# ADC_Core.net
KiCad netlist of a schematic drawn in Altium Designer
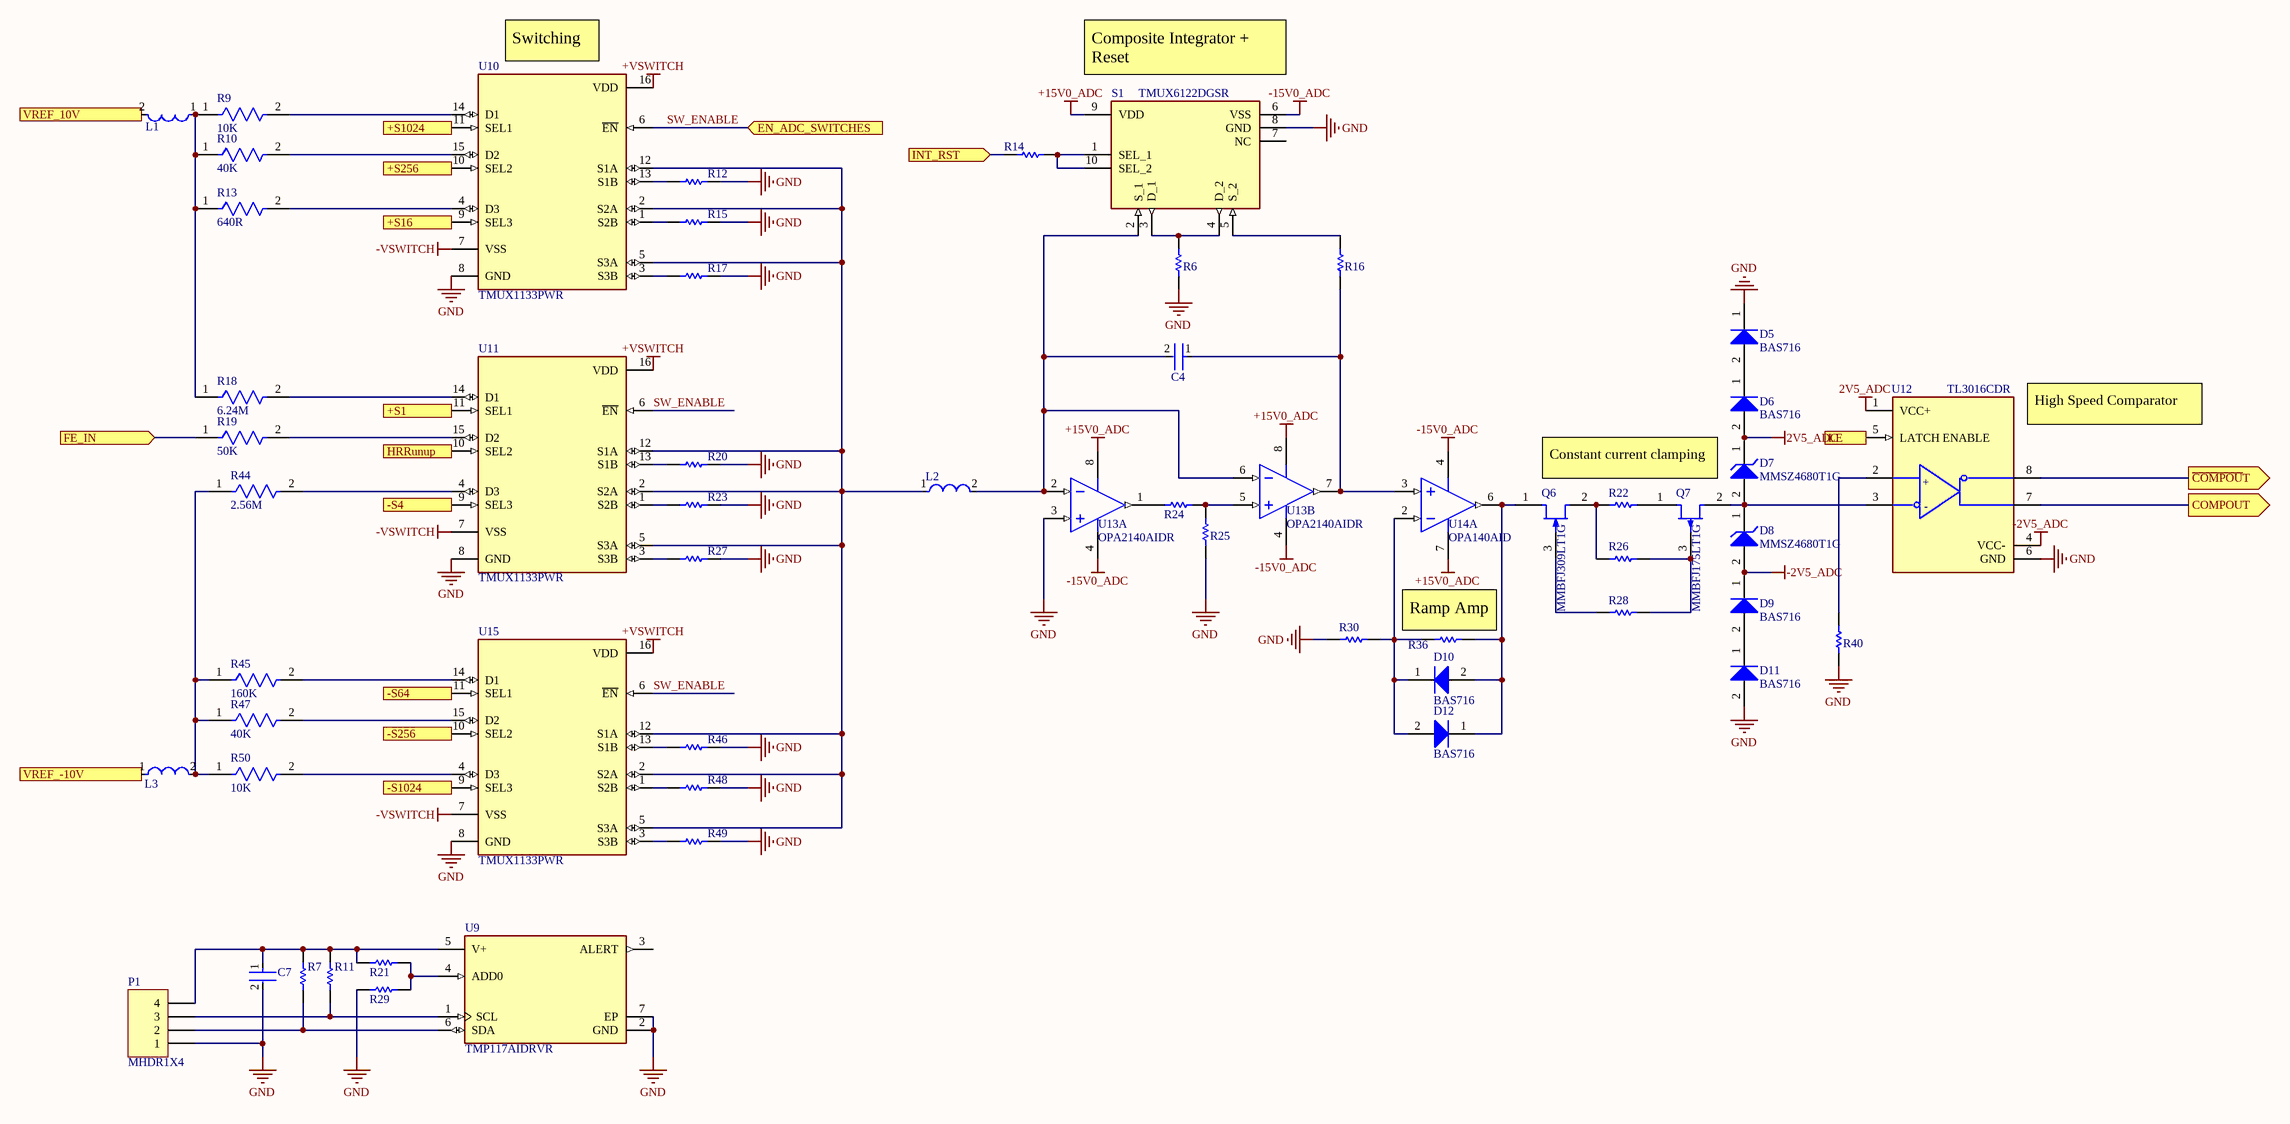
[diagram p0: ADC_Core.SchDoc]

(export (version "E")
  (design (tool "Eeschema 10.0.6"))
  (components
    (comp (ref "C4")
      (value "C1206C331J5GACTU")
      (footprint "FP-C1206C-EB-MFG")
      (description "CAP CER 330PF 50V 5% NP0 1206")
      (fields
        (field (name "MANUFACTURER") "KEMET")
        (field (name "OCTOPART") "https://octopart.com/c1206c331j5gactu-kemet-3859988")
      )
      (libsource (lib "Altium Content Vault") (part "b4654b650e69147ec39a6b967a45e02"))
    )
    (comp (ref "C7")
      (value "C0402C104K8PACTU")
      (footprint "FP-C0402-BB-MFG")
      (description "C0402 0.10 μF X5R 10.00% 10 V")
      (fields (field (name "MANUFACTURER") "Kemet"))
      (libsource (lib "Altium Content Vault") (part "b4654b650e69147ec39a6b967a45e02"))
    )
    (comp (ref "D5")
      (value "BAS716")
      (footprint "ONSC-SOD-523-2-502-01_V")
      (description "Schottky Barrier Diode, 2-Pin SOD-523, Pb-Free, Tape and Reel")
      (fields (field (name "PARTNUMBER") "BAT54XV2T5G") (field (name "MANUFACTURER") "On Semiconductor"))
      (libsource (lib "Altium Content Vault") (part "ONSC-D-K1A2-2"))
    )
    (comp (ref "D6")
      (value "BAS716")
      (footprint "ONSC-SOD-523-2-502-01_V")
      (description "Schottky Barrier Diode, 2-Pin SOD-523, Pb-Free, Tape and Reel")
      (fields (field (name "PARTNUMBER") "BAT54XV2T5G") (field (name "MANUFACTURER") "On Semiconductor"))
      (libsource (lib "Altium Content Vault") (part "ONSC-D-K1A2-2"))
    )
    (comp (ref "D7")
      (value "MMSZ4680T1G")
      (footprint "ONSC-SOD-123-2-425-04_V")
      (description "Zener Voltage Regulator, 500 mW, 2-Pin SOD-123, Pb-Free, Tape and Reel")
      (fields (field (name "MANUFACTURER") "On Semiconductor"))
      (libsource (lib "Altium Content Vault") (part "ONSC-K1A2-2"))
    )
    (comp (ref "D8")
      (value "MMSZ4680T1G")
      (footprint "ONSC-SOD-123-2-425-04_V")
      (description "Zener Voltage Regulator, 500 mW, 2-Pin SOD-123, Pb-Free, Tape and Reel")
      (fields (field (name "MANUFACTURER") "On Semiconductor"))
      (libsource (lib "Altium Content Vault") (part "ONSC-K1A2-2"))
    )
    (comp (ref "D9")
      (value "BAS716")
      (footprint "ONSC-SOD-523-2-502-01_V")
      (description "Schottky Barrier Diode, 2-Pin SOD-523, Pb-Free, Tape and Reel")
      (fields (field (name "PARTNUMBER") "BAT54XV2T5G") (field (name "MANUFACTURER") "On Semiconductor"))
      (libsource (lib "Altium Content Vault") (part "ONSC-D-K1A2-2"))
    )
    (comp (ref "D10")
      (value "BAS716")
      (footprint "ONSC-SOD-523-2-502-01_V")
      (description "Schottky Barrier Diode, 2-Pin SOD-523, Pb-Free, Tape and Reel")
      (fields (field (name "PARTNUMBER") "BAT54XV2T5G") (field (name "MANUFACTURER") "On Semiconductor"))
      (libsource (lib "Altium Content Vault") (part "ONSC-D-K1A2-2"))
    )
    (comp (ref "D11")
      (value "BAS716")
      (footprint "ONSC-SOD-523-2-502-01_V")
      (description "Schottky Barrier Diode, 2-Pin SOD-523, Pb-Free, Tape and Reel")
      (fields (field (name "PARTNUMBER") "BAT54XV2T5G") (field (name "MANUFACTURER") "On Semiconductor"))
      (libsource (lib "Altium Content Vault") (part "ONSC-D-K1A2-2"))
    )
    (comp (ref "D12")
      (value "BAS716")
      (footprint "ONSC-SOD-523-2-502-01_V")
      (description "Schottky Barrier Diode, 2-Pin SOD-523, Pb-Free, Tape and Reel")
      (fields (field (name "PARTNUMBER") "BAT54XV2T5G") (field (name "MANUFACTURER") "On Semiconductor"))
      (libsource (lib "Altium Content Vault") (part "ONSC-D-K1A2-2"))
    )
    (comp (ref "L1")
      (value "LQW15ANR10J00D")
      (footprint "FP-LQW15AN_00-W0_5-0_1-MFG")
      (description "Wire Wound RF Inductor 100nH ±5% 120mA 2.52Ω 0402 (1005)")
      (fields (field (name "TOLERANCE") "5%"))
      (libsource (lib "Altium Content Vault") (part "725321dda6339637d4d059423bc1c3c"))
    )
    (comp (ref "L2")
      (value "LQW15ANR10J00D")
      (footprint "FP-LQW15AN_00-W0_5-0_1-MFG")
      (description "Wire Wound RF Inductor 100nH ±5% 120mA 2.52Ω 0402 (1005)")
      (fields (field (name "TOLERANCE") "5%"))
      (libsource (lib "Altium Content Vault") (part "725321dda6339637d4d059423bc1c3c"))
    )
    (comp (ref "L3")
      (value "LQW15ANR10J00D")
      (footprint "FP-LQW15AN_00-W0_5-0_1-MFG")
      (description "Wire Wound RF Inductor 100nH ±5% 120mA 2.52Ω 0402 (1005)")
      (fields (field (name "TOLERANCE") "5%"))
      (libsource (lib "Altium Content Vault") (part "725321dda6339637d4d059423bc1c3c"))
    )
    (comp (ref "P1")
      (value "MHDR1X4")
      (footprint "MHDR1X4")
      (description "Header, 4-Pin")
      (fields (field (name "PUBLISHER") "Altium Limited"))
      (libsource (lib "Miscellaneous Connectors") (part "MHDR1X4"))
    )
    (comp (ref "Q6")
      (value "MMBFJ309LT1G")
      (footprint "ONSC-SOT-23-3-318-08_V")
      (description "JFET - VHF / UHF Amplifier Transistor, N-Channel, 3-Pin SOT-23, Pb-Free, Tape and Reel")
      (fields (field (name "MANUFACTURER") "On Semiconductor"))
      (libsource (lib "Altium Content Vault") (part "ONSC-JFET-D1S2G3-3-B"))
    )
    (comp (ref "Q7")
      (value "MMBFJ175LT1G")
      (footprint "ONSC-SOT-23-3-318-08_V")
      (description "JFET Chopper, P-Channel - Depletion, 3-Pin SOT-23, Pb-Free, Tape and Reel")
      (fields (field (name "MANUFACTURER") "On Semiconductor"))
      (libsource (lib "Altium Content Vault") (part "ONSC-JFET-D1S2G3-3-C"))
    )
    (comp (ref "R6")
      (value "ERJ-3GEYJ202V")
      (footprint "RESC1608X55X30ML15T15")
      (fields (field (name "MANUFACTURER") "Panasonic"))
      (libsource (lib "Altium Content Vault") (part "RES"))
    )
    (comp (ref "R7")
      (value "CRCW04021K20FKED")
      (footprint "RESC1005X40X25NL05T05")
      (fields (field (name "MANUFACTURER") "Vishay Dale"))
      (libsource (lib "Altium Content Vault") (part "RES"))
    )
    (comp (ref "R9")
      (value "10K")
      (footprint "FP-RC1206-MFG")
      (description "RES SMD 0 OHM JUMPER 1/4W 1206")
      (fields
        (field (name "MANUFACTURER PART NUMBER") "RC1206JR-070RL")
        (field (name "MANUFACTURER") "YAGEO")
      )
      (libsource (lib "Altium Content Vault") (part "1029c3af85768c4190bb7ad29bc67b5"))
    )
    (comp (ref "R10")
      (value "40K")
      (footprint "FP-RC1206-MFG")
      (description "RES SMD 0 OHM JUMPER 1/4W 1206")
      (fields
        (field (name "MANUFACTURER PART NUMBER") "RC1206JR-070RL")
        (field (name "MANUFACTURER") "YAGEO")
      )
      (libsource (lib "Altium Content Vault") (part "1029c3af85768c4190bb7ad29bc67b5"))
    )
    (comp (ref "R11")
      (value "CRCW04021K20FKED")
      (footprint "RESC1005X40X25NL05T05")
      (fields (field (name "MANUFACTURER") "Vishay Dale"))
      (libsource (lib "Altium Content Vault") (part "RES"))
    )
    (comp (ref "R12")
      (value "ERJ-3GEYJ202V")
      (footprint "RESC1608X55X30ML15T15")
      (fields (field (name "MANUFACTURER") "Panasonic"))
      (libsource (lib "Altium Content Vault") (part "RES"))
    )
    (comp (ref "R13")
      (value "640R")
      (footprint "FP-RC1206-MFG")
      (description "RES SMD 0 OHM JUMPER 1/4W 1206")
      (fields
        (field (name "MANUFACTURER PART NUMBER") "RC1206JR-070RL")
        (field (name "MANUFACTURER") "YAGEO")
      )
      (libsource (lib "Altium Content Vault") (part "1029c3af85768c4190bb7ad29bc67b5"))
    )
    (comp (ref "R14")
      (value "ERJ-3GEYJ202V")
      (footprint "RESC1608X55X30ML15T15")
      (fields (field (name "MANUFACTURER") "Panasonic"))
      (libsource (lib "Altium Content Vault") (part "RES"))
    )
    (comp (ref "R15")
      (value "ERJ-3GEYJ202V")
      (footprint "RESC1608X55X30ML15T15")
      (fields (field (name "MANUFACTURER") "Panasonic"))
      (libsource (lib "Altium Content Vault") (part "RES"))
    )
    (comp (ref "R16")
      (value "ERJ-3GEYJ202V")
      (footprint "RESC1608X55X30ML15T15")
      (fields (field (name "MANUFACTURER") "Panasonic"))
      (libsource (lib "Altium Content Vault") (part "RES"))
    )
    (comp (ref "R17")
      (value "ERJ-3GEYJ202V")
      (footprint "RESC1608X55X30ML15T15")
      (fields (field (name "MANUFACTURER") "Panasonic"))
      (libsource (lib "Altium Content Vault") (part "RES"))
    )
    (comp (ref "R18")
      (value "6.24M")
      (footprint "FP-RC1206-MFG")
      (description "RES SMD 0 OHM JUMPER 1/4W 1206")
      (fields
        (field (name "MANUFACTURER PART NUMBER") "RC1206JR-070RL")
        (field (name "MANUFACTURER") "YAGEO")
      )
      (libsource (lib "Altium Content Vault") (part "1029c3af85768c4190bb7ad29bc67b5"))
    )
    (comp (ref "R19")
      (value "50K")
      (footprint "FP-RC1206-MFG")
      (description "RES SMD 0 OHM JUMPER 1/4W 1206")
      (fields
        (field (name "MANUFACTURER PART NUMBER") "RC1206JR-070RL")
        (field (name "MANUFACTURER") "YAGEO")
      )
      (libsource (lib "Altium Content Vault") (part "1029c3af85768c4190bb7ad29bc67b5"))
    )
    (comp (ref "R20")
      (value "ERJ-3GEYJ202V")
      (footprint "RESC1608X55X30ML15T15")
      (fields (field (name "MANUFACTURER") "Panasonic"))
      (libsource (lib "Altium Content Vault") (part "RES"))
    )
    (comp (ref "R21")
      (value "CRCW04021K20FKED")
      (footprint "RESC1005X40X25NL05T05")
      (fields (field (name "MANUFACTURER") "Vishay Dale"))
      (libsource (lib "Altium Content Vault") (part "RES"))
    )
    (comp (ref "R22")
      (value "ERJ-3GEYJ202V")
      (footprint "RESC1608X55X30ML15T15")
      (fields (field (name "MANUFACTURER") "Panasonic"))
      (libsource (lib "Altium Content Vault") (part "RES"))
    )
    (comp (ref "R23")
      (value "ERJ-3GEYJ202V")
      (footprint "RESC1608X55X30ML15T15")
      (fields (field (name "MANUFACTURER") "Panasonic"))
      (libsource (lib "Altium Content Vault") (part "RES"))
    )
    (comp (ref "R24")
      (value "ERJ-3GEYJ202V")
      (footprint "RESC1608X55X30ML15T15")
      (fields (field (name "MANUFACTURER") "Panasonic"))
      (libsource (lib "Altium Content Vault") (part "RES"))
    )
    (comp (ref "R25")
      (value "ERJ-3GEYJ202V")
      (footprint "RESC1608X55X30ML15T15")
      (fields (field (name "MANUFACTURER") "Panasonic"))
      (libsource (lib "Altium Content Vault") (part "RES"))
    )
    (comp (ref "R26")
      (value "ERJ-3EKF4220V")
      (footprint "RESC1608X55X30ML15T15")
      (fields (field (name "MANUFACTURER") "Panasonic"))
      (libsource (lib "Altium Content Vault") (part "RES"))
    )
    (comp (ref "R27")
      (value "ERJ-3GEYJ202V")
      (footprint "RESC1608X55X30ML15T15")
      (fields (field (name "MANUFACTURER") "Panasonic"))
      (libsource (lib "Altium Content Vault") (part "RES"))
    )
    (comp (ref "R28")
      (value "ERJ-3GEYJ202V")
      (footprint "RESC1608X55X30ML15T15")
      (fields (field (name "MANUFACTURER") "Panasonic"))
      (libsource (lib "Altium Content Vault") (part "RES"))
    )
    (comp (ref "R29")
      (value "CRCW04021K20FKED")
      (footprint "RESC1005X40X25NL05T05")
      (fields (field (name "MANUFACTURER") "Vishay Dale"))
      (libsource (lib "Altium Content Vault") (part "RES"))
    )
    (comp (ref "R30")
      (value "ERJ-3GEYJ202V")
      (footprint "RESC1608X55X30ML15T15")
      (fields (field (name "MANUFACTURER") "Panasonic"))
      (libsource (lib "Altium Content Vault") (part "RES"))
    )
    (comp (ref "R36")
      (value "ERJ-3GEYJ202V")
      (footprint "RESC1608X55X30ML15T15")
      (fields (field (name "MANUFACTURER") "Panasonic"))
      (libsource (lib "Altium Content Vault") (part "RES"))
    )
    (comp (ref "R40")
      (value "ERJ-3GEYJ202V")
      (footprint "RESC1608X55X30ML15T15")
      (fields (field (name "MANUFACTURER") "Panasonic"))
      (libsource (lib "Altium Content Vault") (part "RES"))
    )
    (comp (ref "R44")
      (value "2.56M")
      (footprint "FP-RC1206-MFG")
      (description "RES SMD 0 OHM JUMPER 1/4W 1206")
      (fields
        (field (name "MANUFACTURER PART NUMBER") "RC1206JR-070RL")
        (field (name "MANUFACTURER") "YAGEO")
      )
      (libsource (lib "Altium Content Vault") (part "1029c3af85768c4190bb7ad29bc67b5"))
    )
    (comp (ref "R45")
      (value "160K")
      (footprint "FP-RC1206-MFG")
      (description "RES SMD 0 OHM JUMPER 1/4W 1206")
      (fields
        (field (name "MANUFACTURER PART NUMBER") "RC1206JR-070RL")
        (field (name "MANUFACTURER") "YAGEO")
      )
      (libsource (lib "Altium Content Vault") (part "1029c3af85768c4190bb7ad29bc67b5"))
    )
    (comp (ref "R46")
      (value "ERJ-3GEYJ202V")
      (footprint "RESC1608X55X30ML15T15")
      (fields (field (name "MANUFACTURER") "Panasonic"))
      (libsource (lib "Altium Content Vault") (part "RES"))
    )
    (comp (ref "R47")
      (value "40K")
      (footprint "FP-RC1206-MFG")
      (description "RES SMD 0 OHM JUMPER 1/4W 1206")
      (fields
        (field (name "MANUFACTURER PART NUMBER") "RC1206JR-070RL")
        (field (name "MANUFACTURER") "YAGEO")
      )
      (libsource (lib "Altium Content Vault") (part "1029c3af85768c4190bb7ad29bc67b5"))
    )
    (comp (ref "R48")
      (value "ERJ-3GEYJ202V")
      (footprint "RESC1608X55X30ML15T15")
      (fields (field (name "MANUFACTURER") "Panasonic"))
      (libsource (lib "Altium Content Vault") (part "RES"))
    )
    (comp (ref "R49")
      (value "ERJ-3GEYJ202V")
      (footprint "RESC1608X55X30ML15T15")
      (fields (field (name "MANUFACTURER") "Panasonic"))
      (libsource (lib "Altium Content Vault") (part "RES"))
    )
    (comp (ref "R50")
      (value "10K")
      (footprint "FP-RC1206-MFG")
      (description "RES SMD 0 OHM JUMPER 1/4W 1206")
      (fields
        (field (name "MANUFACTURER PART NUMBER") "RC1206JR-070RL")
        (field (name "MANUFACTURER") "YAGEO")
      )
      (libsource (lib "Altium Content Vault") (part "1029c3af85768c4190bb7ad29bc67b5"))
    )
    (comp (ref "S1")
      (value "TMUX6122DGSR")
      (footprint "SOP50P490X110-10N")
      (description "Switch")
      (fields (field (name "MOUSER PART NUMBER") "595-TMUX6122DGSR"))
      (libsource (lib "SamacSys") (part "TMUX6122DGSR"))
    )
    (comp (ref "U9")
      (value "TMP117AIDRVR")
      (footprint "FP-DRV0006A-MFG")
      (description "TEMPERATURE SENSOR")
      (fields
        (field (name "OCTOPART") "https://octopart.com/tmp117aidrvr-texas+instruments-95511044")
        (field (name "MANUFACTURER") "Texas Instruments")
      )
      (libsource (lib "Altium Content Vault") (part "bceab6869a9cb85cf5675529ee35ce4"))
    )
    (comp (ref "U10")
      (value "TMUX1133PWR")
      (footprint "FP-PW0016A-MFG")
      (description "IC SWITCH")
      (libsource (lib "Altium Content Vault") (part "5e179f31be763ae3d099545761d6507"))
    )
    (comp (ref "U11")
      (value "TMUX1133PWR")
      (footprint "FP-PW0016A-MFG")
      (description "IC SWITCH")
      (libsource (lib "Altium Content Vault") (part "5e179f31be763ae3d099545761d6507"))
    )
    (comp (ref "U12")
      (value "TL3016CDR")
      (footprint "FP-D0008A-IPC_A")
      (description "IC PREC COMP ULTRA-FAST 8-SOIC")
      (libsource (lib "Altium Content Vault") (part "2aa60c65b50ba0c0e5c8abbc6482fcd"))
    )
    (comp (ref "U13")
      (value "OPA2140AIDR")
      (footprint "D0008A_M")
      (fields (field (name "MANUFACTURER") "Texas Instruments"))
      (libsource (lib "Altium Content Vault") (part "TI-OPA-8_2"))
    )
    (comp (ref "U14")
      (value "OPA140AID")
      (footprint "D0008A_M")
      (fields (field (name "MANUFACTURER") "Texas Instruments"))
      (libsource (lib "Altium Content Vault") (part "TI-OPA-8_1"))
    )
    (comp (ref "U15")
      (value "TMUX1133PWR")
      (footprint "FP-PW0016A-MFG")
      (description "IC SWITCH")
      (libsource (lib "Altium Content Vault") (part "5e179f31be763ae3d099545761d6507"))
    )
  )
  (nets
    (net (code "1") (name "+15V0_ADC") (class "Default")
      (node (ref "S1") (pin "9") (pinfunction "VDD_9") (pintype "power_in"))
      (node (ref "U13") (pin "8") (pinfunction "V+_8") (pintype "power_in"))
      (node (ref "U14") (pin "7") (pinfunction "V+_7") (pintype "power_in"))
    )
    (net (code "2") (name "+VSWITCH") (class "Default")
      (node (ref "U10") (pin "16") (pinfunction "VDD_16") (pintype "power_in"))
      (node (ref "U11") (pin "16") (pinfunction "VDD_16") (pintype "power_in"))
      (node (ref "U15") (pin "16") (pinfunction "VDD_16") (pintype "power_in"))
    )
    (net (code "3") (name "-2V5_ADC") (class "Default")
      (node (ref "D8") (pin "2") (pinfunction "A_2") (pintype "passive"))
      (node (ref "D9") (pin "1") (pinfunction "K_1") (pintype "passive"))
      (node (ref "U12") (pin "4") (pinfunction "VCC-_4") (pintype "power_in"))
    )
    (net (code "4") (name "-15V0_ADC") (class "Default")
      (node (ref "S1") (pin "6") (pinfunction "VSS_6") (pintype "power_in"))
      (node (ref "U13") (pin "4") (pinfunction "V-_4") (pintype "power_in"))
      (node (ref "U14") (pin "4") (pinfunction "V-_4") (pintype "power_in"))
    )
    (net (code "5") (name "-VSWITCH") (class "Default")
      (node (ref "U10") (pin "7") (pinfunction "VSS_7") (pintype "power_in"))
      (node (ref "U11") (pin "7") (pinfunction "VSS_7") (pintype "power_in"))
      (node (ref "U15") (pin "7") (pinfunction "VSS_7") (pintype "power_in"))
    )
    (net (code "6") (name "/+S1") (class "Default")
      (node (ref "U11") (pin "11") (pinfunction "SEL1_11") (pintype "input"))
    )
    (net (code "7") (name "/+S16") (class "Default")
      (node (ref "U10") (pin "9") (pinfunction "SEL3_9") (pintype "input"))
    )
    (net (code "8") (name "/+S256") (class "Default")
      (node (ref "U10") (pin "10") (pinfunction "SEL2_10") (pintype "input"))
    )
    (net (code "9") (name "/+S1024") (class "Default")
      (node (ref "U10") (pin "11") (pinfunction "SEL1_11") (pintype "input"))
    )
    (net (code "10") (name "/-S4") (class "Default")
      (node (ref "U11") (pin "9") (pinfunction "SEL3_9") (pintype "input"))
    )
    (net (code "11") (name "/-S64") (class "Default")
      (node (ref "U15") (pin "11") (pinfunction "SEL1_11") (pintype "input"))
    )
    (net (code "12") (name "/-S256") (class "Default")
      (node (ref "U15") (pin "10") (pinfunction "SEL2_10") (pintype "input"))
    )
    (net (code "13") (name "/-S1024") (class "Default")
      (node (ref "U15") (pin "9") (pinfunction "SEL3_9") (pintype "input"))
    )
    (net (code "14") (name "/COMPOUT") (class "Default")
      (node (ref "U12") (pin "7") (pinfunction "Q_OUT_7") (pintype "passive"))
    )
    (net (code "15") (name "/FE_IN") (class "Default")
      (node (ref "R19") (pin "1") (pinfunction "1_1") (pintype "passive"))
    )
    (net (code "16") (name "/HRRunup") (class "Default")
      (node (ref "U11") (pin "10") (pinfunction "SEL2_10") (pintype "input"))
    )
    (net (code "17") (name "/INT_RST") (class "Default")
      (node (ref "R14") (pin "2") (pinfunction "2_2") (pintype "passive"))
    )
    (net (code "18") (name "/LE") (class "Default")
      (node (ref "U12") (pin "5") (pinfunction "LATCH_ENABLE_5") (pintype "input"))
    )
    (net (code "19") (name "/SW_ENABLE") (class "Default")
      (node (ref "U10") (pin "6") (pinfunction "~{EN}_6") (pintype "input"))
      (node (ref "U11") (pin "6") (pinfunction "~{EN}_6") (pintype "input"))
      (node (ref "U15") (pin "6") (pinfunction "~{EN}_6") (pintype "input"))
    )
    (net (code "20") (name "/VREF_-10V") (class "Default")
      (node (ref "L3") (pin "1") (pinfunction "1_1") (pintype "passive"))
    )
    (net (code "21") (name "/VREF_10V") (class "Default")
      (node (ref "L1") (pin "2") (pinfunction "2_2") (pintype "passive"))
    )
    (net (code "22") (name "/~{COMPOU}T") (class "Default")
      (node (ref "U12") (pin "8") (pinfunction "~{Q_OUT}_8") (pintype "passive"))
    )
    (net (code "23") (name "2V5_ADC") (class "Default")
      (node (ref "D6") (pin "2") (pinfunction "A_2") (pintype "passive"))
      (node (ref "D7") (pin "1") (pinfunction "K_1") (pintype "passive"))
      (node (ref "U12") (pin "1") (pinfunction "VCC+_1") (pintype "power_in"))
    )
    (net (code "24") (name "GND") (class "Default")
      (node (ref "C7") (pin "2") (pinfunction "2_2") (pintype "passive"))
      (node (ref "D11") (pin "2") (pinfunction "A_2") (pintype "passive"))
      (node (ref "D5") (pin "1") (pinfunction "K_1") (pintype "passive"))
      (node (ref "P1") (pin "1") (pinfunction "1_1") (pintype "passive"))
      (node (ref "R12") (pin "2") (pinfunction "2_2") (pintype "passive"))
      (node (ref "R15") (pin "2") (pinfunction "2_2") (pintype "passive"))
      (node (ref "R17") (pin "2") (pinfunction "2_2") (pintype "passive"))
      (node (ref "R20") (pin "2") (pinfunction "2_2") (pintype "passive"))
      (node (ref "R23") (pin "2") (pinfunction "2_2") (pintype "passive"))
      (node (ref "R25") (pin "1") (pinfunction "1_1") (pintype "passive"))
      (node (ref "R27") (pin "2") (pinfunction "2_2") (pintype "passive"))
      (node (ref "R29") (pin "2") (pinfunction "2_2") (pintype "passive"))
      (node (ref "R30") (pin "1") (pinfunction "1_1") (pintype "passive"))
      (node (ref "R40") (pin "1") (pinfunction "1_1") (pintype "passive"))
      (node (ref "R46") (pin "2") (pinfunction "2_2") (pintype "passive"))
      (node (ref "R48") (pin "2") (pinfunction "2_2") (pintype "passive"))
      (node (ref "R49") (pin "2") (pinfunction "2_2") (pintype "passive"))
      (node (ref "R6") (pin "1") (pinfunction "1_1") (pintype "passive"))
      (node (ref "S1") (pin "8") (pinfunction "GND_8") (pintype "power_in"))
      (node (ref "U10") (pin "8") (pinfunction "GND_8") (pintype "power_in"))
      (node (ref "U11") (pin "8") (pinfunction "GND_8") (pintype "power_in"))
      (node (ref "U12") (pin "6") (pinfunction "GND_6") (pintype "power_in"))
      (node (ref "U13") (pin "3") (pinfunction "IN_A+_3") (pintype "input"))
      (node (ref "U15") (pin "8") (pinfunction "GND_8") (pintype "power_in"))
      (node (ref "U9") (pin "2") (pinfunction "GND_2") (pintype "power_in"))
      (node (ref "U9") (pin "7") (pinfunction "EP_7") (pintype "passive"))
    )
    (net (code "25") (name "Net-(D5-A)") (class "Default")
      (node (ref "D5") (pin "2") (pinfunction "A_2") (pintype "passive"))
      (node (ref "D6") (pin "1") (pinfunction "K_1") (pintype "passive"))
    )
    (net (code "26") (name "Net-(D7-A)") (class "Default")
      (node (ref "D7") (pin "2") (pinfunction "A_2") (pintype "passive"))
      (node (ref "D8") (pin "1") (pinfunction "K_1") (pintype "passive"))
      (node (ref "Q7") (pin "2") (pinfunction "S_2") (pintype "passive"))
      (node (ref "U12") (pin "3") (pinfunction "IN-_3") (pintype "tri_state"))
    )
    (net (code "27") (name "Net-(D10-A)") (class "Default")
      (node (ref "D10") (pin "2") (pinfunction "A_2") (pintype "passive"))
      (node (ref "D12") (pin "1") (pinfunction "K_1") (pintype "passive"))
      (node (ref "Q6") (pin "1") (pinfunction "D_1") (pintype "passive"))
      (node (ref "R36") (pin "2") (pinfunction "2_2") (pintype "passive"))
      (node (ref "U14") (pin "6") (pinfunction "OUT_6") (pintype "output"))
    )
    (net (code "28") (name "Net-(D10-K)") (class "Default")
      (node (ref "D10") (pin "1") (pinfunction "K_1") (pintype "passive"))
      (node (ref "D12") (pin "2") (pinfunction "A_2") (pintype "passive"))
      (node (ref "R30") (pin "2") (pinfunction "2_2") (pintype "passive"))
      (node (ref "R36") (pin "1") (pinfunction "1_1") (pintype "passive"))
      (node (ref "U14") (pin "2") (pinfunction "IN-_2") (pintype "input"))
    )
    (net (code "29") (name "Net-(D11-K)") (class "Default")
      (node (ref "D11") (pin "1") (pinfunction "K_1") (pintype "passive"))
      (node (ref "D9") (pin "2") (pinfunction "A_2") (pintype "passive"))
    )
    (net (code "30") (name "Net-(L1-Pad1)") (class "Default")
      (node (ref "L1") (pin "1") (pinfunction "1_1") (pintype "passive"))
      (node (ref "R10") (pin "1") (pinfunction "1_1") (pintype "passive"))
      (node (ref "R13") (pin "1") (pinfunction "1_1") (pintype "passive"))
      (node (ref "R18") (pin "1") (pinfunction "1_1") (pintype "passive"))
      (node (ref "R9") (pin "1") (pinfunction "1_1") (pintype "passive"))
    )
    (net (code "31") (name "Net-(L3-Pad2)") (class "Default")
      (node (ref "L3") (pin "2") (pinfunction "2_2") (pintype "passive"))
      (node (ref "R44") (pin "1") (pinfunction "1_1") (pintype "passive"))
      (node (ref "R45") (pin "1") (pinfunction "1_1") (pintype "passive"))
      (node (ref "R47") (pin "1") (pinfunction "1_1") (pintype "passive"))
      (node (ref "R50") (pin "1") (pinfunction "1_1") (pintype "passive"))
    )
    (net (code "32") (name "Net-(Q6-G)") (class "Default")
      (node (ref "Q6") (pin "3") (pinfunction "G_3") (pintype "passive"))
      (node (ref "R28") (pin "1") (pinfunction "1_1") (pintype "passive"))
    )
    (net (code "33") (name "Net-(Q6-S)") (class "Default")
      (node (ref "Q6") (pin "2") (pinfunction "S_2") (pintype "passive"))
      (node (ref "R22") (pin "1") (pinfunction "1_1") (pintype "passive"))
      (node (ref "R26") (pin "1") (pinfunction "1_1") (pintype "passive"))
    )
    (net (code "34") (name "Net-(Q7-D)") (class "Default")
      (node (ref "Q7") (pin "1") (pinfunction "D_1") (pintype "passive"))
      (node (ref "R22") (pin "2") (pinfunction "2_2") (pintype "passive"))
    )
    (net (code "35") (name "Net-(Q7-G)") (class "Default")
      (node (ref "Q7") (pin "3") (pinfunction "G_3") (pintype "passive"))
      (node (ref "R26") (pin "2") (pinfunction "2_2") (pintype "passive"))
      (node (ref "R28") (pin "2") (pinfunction "2_2") (pintype "passive"))
    )
    (net (code "36") (name "Net-(S1-D_1)") (class "Default")
      (node (ref "R6") (pin "2") (pinfunction "2_2") (pintype "passive"))
      (node (ref "S1") (pin "3") (pinfunction "D_1_3") (pintype "output"))
      (node (ref "S1") (pin "4") (pinfunction "D_2_4") (pintype "output"))
    )
    (net (code "37") (name "Net-(S1-SEL_1)") (class "Default")
      (node (ref "R14") (pin "1") (pinfunction "1_1") (pintype "passive"))
      (node (ref "S1") (pin "1") (pinfunction "SEL_1_1") (pintype "passive"))
      (node (ref "S1") (pin "10") (pinfunction "SEL_2_10") (pintype "passive"))
    )
    (net (code "38") (name "Net-(S1-S_1)") (class "Default")
      (node (ref "C4") (pin "2") (pinfunction "2_2") (pintype "passive"))
      (node (ref "L2") (pin "2") (pinfunction "2_2") (pintype "passive"))
      (node (ref "S1") (pin "2") (pinfunction "S_1_2") (pintype "input"))
      (node (ref "U13") (pin "2") (pinfunction "IN_A-_2") (pintype "input"))
      (node (ref "U13") (pin "6") (pinfunction "IN_B-_6") (pintype "input"))
    )
    (net (code "39") (name "Net-(S1-S_2)") (class "Default")
      (node (ref "R16") (pin "2") (pinfunction "2_2") (pintype "passive"))
      (node (ref "S1") (pin "5") (pinfunction "S_2_5") (pintype "input"))
    )
    (net (code "40") (name "Net-(U9-ADD0)") (class "Default")
      (node (ref "R21") (pin "1") (pinfunction "1_1") (pintype "passive"))
      (node (ref "R29") (pin "1") (pinfunction "1_1") (pintype "passive"))
      (node (ref "U9") (pin "4") (pinfunction "ADD0_4") (pintype "input"))
    )
    (net (code "41") (name "Net-(U9-SCL)") (class "Default")
      (node (ref "P1") (pin "3") (pinfunction "3_3") (pintype "passive"))
      (node (ref "R11") (pin "1") (pinfunction "1_1") (pintype "passive"))
      (node (ref "U9") (pin "1") (pinfunction "SCL_1") (pintype "input"))
    )
    (net (code "42") (name "Net-(U9-SDA)") (class "Default")
      (node (ref "P1") (pin "2") (pinfunction "2_2") (pintype "passive"))
      (node (ref "R7") (pin "1") (pinfunction "1_1") (pintype "passive"))
      (node (ref "U9") (pin "6") (pinfunction "SDA_6") (pintype "bidirectional"))
    )
    (net (code "43") (name "Net-(U9-V+)") (class "Default")
      (node (ref "C7") (pin "1") (pinfunction "1_1") (pintype "passive"))
      (node (ref "P1") (pin "4") (pinfunction "4_4") (pintype "passive"))
      (node (ref "R11") (pin "2") (pinfunction "2_2") (pintype "passive"))
      (node (ref "R21") (pin "2") (pinfunction "2_2") (pintype "passive"))
      (node (ref "R7") (pin "2") (pinfunction "2_2") (pintype "passive"))
      (node (ref "U9") (pin "5") (pinfunction "V+_5") (pintype "power_in"))
    )
    (net (code "44") (name "Net-(U10-D1)") (class "Default")
      (node (ref "R9") (pin "2") (pinfunction "2_2") (pintype "passive"))
      (node (ref "U10") (pin "14") (pinfunction "D1_14") (pintype "bidirectional"))
    )
    (net (code "45") (name "Net-(U10-D2)") (class "Default")
      (node (ref "R10") (pin "2") (pinfunction "2_2") (pintype "passive"))
      (node (ref "U10") (pin "15") (pinfunction "D2_15") (pintype "bidirectional"))
    )
    (net (code "46") (name "Net-(U10-D3)") (class "Default")
      (node (ref "R13") (pin "2") (pinfunction "2_2") (pintype "passive"))
      (node (ref "U10") (pin "4") (pinfunction "D3_4") (pintype "bidirectional"))
    )
    (net (code "47") (name "Net-(U10-S1A)") (class "Default")
      (node (ref "L2") (pin "1") (pinfunction "1_1") (pintype "passive"))
      (node (ref "U10") (pin "12") (pinfunction "S1A_12") (pintype "bidirectional"))
      (node (ref "U10") (pin "2") (pinfunction "S2A_2") (pintype "bidirectional"))
      (node (ref "U10") (pin "5") (pinfunction "S3A_5") (pintype "bidirectional"))
      (node (ref "U11") (pin "12") (pinfunction "S1A_12") (pintype "bidirectional"))
      (node (ref "U11") (pin "2") (pinfunction "S2A_2") (pintype "bidirectional"))
      (node (ref "U11") (pin "5") (pinfunction "S3A_5") (pintype "bidirectional"))
      (node (ref "U15") (pin "12") (pinfunction "S1A_12") (pintype "bidirectional"))
      (node (ref "U15") (pin "2") (pinfunction "S2A_2") (pintype "bidirectional"))
      (node (ref "U15") (pin "5") (pinfunction "S3A_5") (pintype "bidirectional"))
    )
    (net (code "48") (name "Net-(U10-S1B)") (class "Default")
      (node (ref "R12") (pin "1") (pinfunction "1_1") (pintype "passive"))
      (node (ref "U10") (pin "13") (pinfunction "S1B_13") (pintype "bidirectional"))
    )
    (net (code "49") (name "Net-(U10-S2B)") (class "Default")
      (node (ref "R15") (pin "1") (pinfunction "1_1") (pintype "passive"))
      (node (ref "U10") (pin "1") (pinfunction "S2B_1") (pintype "bidirectional"))
    )
    (net (code "50") (name "Net-(U10-S3B)") (class "Default")
      (node (ref "R17") (pin "1") (pinfunction "1_1") (pintype "passive"))
      (node (ref "U10") (pin "3") (pinfunction "S3B_3") (pintype "bidirectional"))
    )
    (net (code "51") (name "Net-(U11-D1)") (class "Default")
      (node (ref "R18") (pin "2") (pinfunction "2_2") (pintype "passive"))
      (node (ref "U11") (pin "14") (pinfunction "D1_14") (pintype "bidirectional"))
    )
    (net (code "52") (name "Net-(U11-D2)") (class "Default")
      (node (ref "R19") (pin "2") (pinfunction "2_2") (pintype "passive"))
      (node (ref "U11") (pin "15") (pinfunction "D2_15") (pintype "bidirectional"))
    )
    (net (code "53") (name "Net-(U11-D3)") (class "Default")
      (node (ref "R44") (pin "2") (pinfunction "2_2") (pintype "passive"))
      (node (ref "U11") (pin "4") (pinfunction "D3_4") (pintype "bidirectional"))
    )
    (net (code "54") (name "Net-(U11-S1B)") (class "Default")
      (node (ref "R20") (pin "1") (pinfunction "1_1") (pintype "passive"))
      (node (ref "U11") (pin "13") (pinfunction "S1B_13") (pintype "bidirectional"))
    )
    (net (code "55") (name "Net-(U11-S2B)") (class "Default")
      (node (ref "R23") (pin "1") (pinfunction "1_1") (pintype "passive"))
      (node (ref "U11") (pin "1") (pinfunction "S2B_1") (pintype "bidirectional"))
    )
    (net (code "56") (name "Net-(U11-S3B)") (class "Default")
      (node (ref "R27") (pin "1") (pinfunction "1_1") (pintype "passive"))
      (node (ref "U11") (pin "3") (pinfunction "S3B_3") (pintype "bidirectional"))
    )
    (net (code "57") (name "Net-(U12-IN+)") (class "Default")
      (node (ref "R40") (pin "2") (pinfunction "2_2") (pintype "passive"))
      (node (ref "U12") (pin "2") (pinfunction "IN+_2") (pintype "tri_state"))
    )
    (net (code "58") (name "Net-(U13A-OUT_A)") (class "Default")
      (node (ref "R24") (pin "2") (pinfunction "2_2") (pintype "passive"))
      (node (ref "U13") (pin "1") (pinfunction "OUT_A_1") (pintype "output"))
    )
    (net (code "59") (name "Net-(U13B-IN_B+)") (class "Default")
      (node (ref "R24") (pin "1") (pinfunction "1_1") (pintype "passive"))
      (node (ref "R25") (pin "2") (pinfunction "2_2") (pintype "passive"))
      (node (ref "U13") (pin "5") (pinfunction "IN_B+_5") (pintype "input"))
    )
    (net (code "60") (name "Net-(U13B-OUT_B)") (class "Default")
      (node (ref "C4") (pin "1") (pinfunction "1_1") (pintype "passive"))
      (node (ref "R16") (pin "1") (pinfunction "1_1") (pintype "passive"))
      (node (ref "U13") (pin "7") (pinfunction "OUT_B_7") (pintype "output"))
      (node (ref "U14") (pin "3") (pinfunction "IN+_3") (pintype "input"))
    )
    (net (code "61") (name "Net-(U15-D1)") (class "Default")
      (node (ref "R45") (pin "2") (pinfunction "2_2") (pintype "passive"))
      (node (ref "U15") (pin "14") (pinfunction "D1_14") (pintype "bidirectional"))
    )
    (net (code "62") (name "Net-(U15-D2)") (class "Default")
      (node (ref "R47") (pin "2") (pinfunction "2_2") (pintype "passive"))
      (node (ref "U15") (pin "15") (pinfunction "D2_15") (pintype "bidirectional"))
    )
    (net (code "63") (name "Net-(U15-D3)") (class "Default")
      (node (ref "R50") (pin "2") (pinfunction "2_2") (pintype "passive"))
      (node (ref "U15") (pin "4") (pinfunction "D3_4") (pintype "bidirectional"))
    )
    (net (code "64") (name "Net-(U15-S1B)") (class "Default")
      (node (ref "R46") (pin "1") (pinfunction "1_1") (pintype "passive"))
      (node (ref "U15") (pin "13") (pinfunction "S1B_13") (pintype "bidirectional"))
    )
    (net (code "65") (name "Net-(U15-S2B)") (class "Default")
      (node (ref "R48") (pin "1") (pinfunction "1_1") (pintype "passive"))
      (node (ref "U15") (pin "1") (pinfunction "S2B_1") (pintype "bidirectional"))
    )
    (net (code "66") (name "Net-(U15-S3B)") (class "Default")
      (node (ref "R49") (pin "1") (pinfunction "1_1") (pintype "passive"))
      (node (ref "U15") (pin "3") (pinfunction "S3B_3") (pintype "bidirectional"))
    )
    (net (code "67") (name "unconnected-(S1-NC-Pad7)") (class "Default")
      (node (ref "S1") (pin "7") (pinfunction "NC_7") (pintype "passive"))
    )
    (net (code "68") (name "unconnected-(U9-ALERT-Pad3)") (class "Default")
      (node (ref "U9") (pin "3") (pinfunction "ALERT_3") (pintype "output"))
    )
  )
)
